# HighVoltageMeasurementModule_1000V.net
KiCad netlist of a schematic drawn in EAGLE
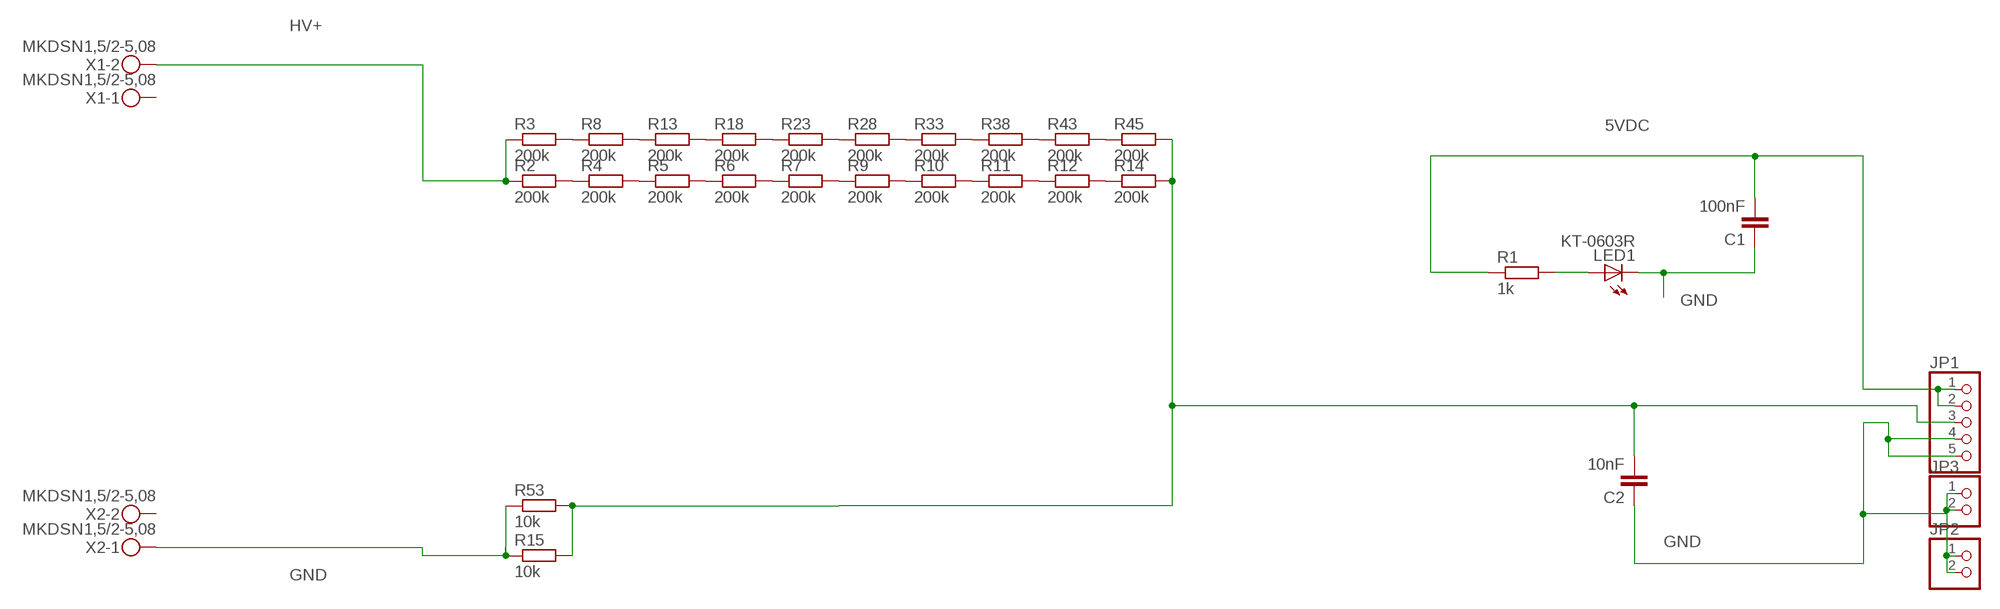
[diagram p0: schematic, sheet 1]

(export (version "E")
  (design (tool "Eeschema 10.0.6"))
  (components
    (comp (ref "C1")
      (value "100nF")
      (footprint "eagle-import:C0805")
      (libsource (lib "eagle-import") (part "C-EUC0805"))
    )
    (comp (ref "C2")
      (value "10nF")
      (footprint "eagle-import:C0805")
      (libsource (lib "eagle-import") (part "C-EUC0805"))
    )
    (comp (ref "JP1")
      (value "PINHD-1X5")
      (footprint "eagle-import:1X05")
      (libsource (lib "eagle-import") (part "PINHD-1X5"))
    )
    (comp (ref "JP2")
      (value "PINHD-1X2")
      (footprint "eagle-import:1X02")
      (libsource (lib "eagle-import") (part "PINHD-1X2"))
    )
    (comp (ref "JP3")
      (value "PINHD-1X2")
      (footprint "eagle-import:1X02")
      (libsource (lib "eagle-import") (part "PINHD-1X2"))
    )
    (comp (ref "LED1")
      (value "KT-0603R")
      (footprint "eagle-import:CHIPLED_0603")
      (libsource (lib "eagle-import") (part "LEDCHIPLED_0603"))
    )
    (comp (ref "R1")
      (value "1k")
      (footprint "eagle-import:R0805")
      (libsource (lib "eagle-import") (part "R-EU_R0805"))
    )
    (comp (ref "R2")
      (value "200k")
      (footprint "eagle-import:R0805")
      (libsource (lib "eagle-import") (part "R-EU_R0805"))
    )
    (comp (ref "R3")
      (value "200k")
      (footprint "eagle-import:R0805")
      (libsource (lib "eagle-import") (part "R-EU_R0805"))
    )
    (comp (ref "R4")
      (value "200k")
      (footprint "eagle-import:R0805")
      (libsource (lib "eagle-import") (part "R-EU_R0805"))
    )
    (comp (ref "R5")
      (value "200k")
      (footprint "eagle-import:R0805")
      (libsource (lib "eagle-import") (part "R-EU_R0805"))
    )
    (comp (ref "R6")
      (value "200k")
      (footprint "eagle-import:R0805")
      (libsource (lib "eagle-import") (part "R-EU_R0805"))
    )
    (comp (ref "R7")
      (value "200k")
      (footprint "eagle-import:R0805")
      (libsource (lib "eagle-import") (part "R-EU_R0805"))
    )
    (comp (ref "R8")
      (value "200k")
      (footprint "eagle-import:R0805")
      (libsource (lib "eagle-import") (part "R-EU_R0805"))
    )
    (comp (ref "R9")
      (value "200k")
      (footprint "eagle-import:R0805")
      (libsource (lib "eagle-import") (part "R-EU_R0805"))
    )
    (comp (ref "R10")
      (value "200k")
      (footprint "eagle-import:R0805")
      (libsource (lib "eagle-import") (part "R-EU_R0805"))
    )
    (comp (ref "R11")
      (value "200k")
      (footprint "eagle-import:R0805")
      (libsource (lib "eagle-import") (part "R-EU_R0805"))
    )
    (comp (ref "R12")
      (value "200k")
      (footprint "eagle-import:R0805")
      (libsource (lib "eagle-import") (part "R-EU_R0805"))
    )
    (comp (ref "R13")
      (value "200k")
      (footprint "eagle-import:R0805")
      (libsource (lib "eagle-import") (part "R-EU_R0805"))
    )
    (comp (ref "R14")
      (value "200k")
      (footprint "eagle-import:R0805")
      (libsource (lib "eagle-import") (part "R-EU_R0805"))
    )
    (comp (ref "R15")
      (value "10k")
      (footprint "eagle-import:R0805")
      (libsource (lib "eagle-import") (part "R-EU_R0805"))
    )
    (comp (ref "R18")
      (value "200k")
      (footprint "eagle-import:R0805")
      (libsource (lib "eagle-import") (part "R-EU_R0805"))
    )
    (comp (ref "R23")
      (value "200k")
      (footprint "eagle-import:R0805")
      (libsource (lib "eagle-import") (part "R-EU_R0805"))
    )
    (comp (ref "R28")
      (value "200k")
      (footprint "eagle-import:R0805")
      (libsource (lib "eagle-import") (part "R-EU_R0805"))
    )
    (comp (ref "R33")
      (value "200k")
      (footprint "eagle-import:R0805")
      (libsource (lib "eagle-import") (part "R-EU_R0805"))
    )
    (comp (ref "R38")
      (value "200k")
      (footprint "eagle-import:R0805")
      (libsource (lib "eagle-import") (part "R-EU_R0805"))
    )
    (comp (ref "R43")
      (value "200k")
      (footprint "eagle-import:R0805")
      (libsource (lib "eagle-import") (part "R-EU_R0805"))
    )
    (comp (ref "R45")
      (value "200k")
      (footprint "eagle-import:R0805")
      (libsource (lib "eagle-import") (part "R-EU_R0805"))
    )
    (comp (ref "R53")
      (value "10k")
      (footprint "eagle-import:R0805")
      (libsource (lib "eagle-import") (part "R-EU_R0805"))
    )
    (comp (ref "X1")
      (value "MKDSN1,5/2-5,08")
      (footprint "eagle-import:MKDSN1,5_2-5,08")
      (libsource (lib "eagle-import") (part "MKDSN1,5/2-5,08"))
    )
    (comp (ref "X2")
      (value "MKDSN1,5/2-5,08")
      (footprint "eagle-import:MKDSN1,5_2-5,08")
      (libsource (lib "eagle-import") (part "MKDSN1,5/2-5,08"))
    )
  )
  (nets
    (net (code "1") (name "/5VDC") (class "Default")
      (node (ref "C1") (pin "2") (pinfunction "2_2") (pintype "passive"))
      (node (ref "JP1") (pin "1") (pinfunction "1_1") (pintype "passive"))
      (node (ref "JP1") (pin "2") (pinfunction "2_2") (pintype "passive"))
      (node (ref "R1") (pin "1") (pinfunction "1_1") (pintype "passive"))
    )
    (net (code "2") (name "/GND") (class "Default")
      (node (ref "C1") (pin "1") (pinfunction "1_1") (pintype "passive"))
      (node (ref "C2") (pin "1") (pinfunction "1_1") (pintype "passive"))
      (node (ref "JP1") (pin "4") (pinfunction "4_4") (pintype "passive"))
      (node (ref "JP1") (pin "5") (pinfunction "5_5") (pintype "passive"))
      (node (ref "JP2") (pin "1") (pinfunction "1_1") (pintype "passive"))
      (node (ref "JP2") (pin "2") (pinfunction "2_2") (pintype "passive"))
      (node (ref "JP3") (pin "1") (pinfunction "1_1") (pintype "passive"))
      (node (ref "JP3") (pin "2") (pinfunction "2_2") (pintype "passive"))
      (node (ref "LED1") (pin "C") (pinfunction "C_C") (pintype "passive"))
      (node (ref "R15") (pin "1") (pinfunction "1_1") (pintype "passive"))
      (node (ref "R53") (pin "1") (pinfunction "1_1") (pintype "passive"))
      (node (ref "X2") (pin "1") (pinfunction "KL_1") (pintype "passive"))
    )
    (net (code "3") (name "/HV+") (class "Default")
      (node (ref "R2") (pin "1") (pinfunction "1_1") (pintype "passive"))
      (node (ref "R3") (pin "1") (pinfunction "1_1") (pintype "passive"))
      (node (ref "X1") (pin "2") (pinfunction "KL_2") (pintype "passive"))
    )
    (net (code "4") (name "Net-(C2-Pad2)") (class "Default")
      (node (ref "C2") (pin "2") (pinfunction "2_2") (pintype "passive"))
      (node (ref "JP1") (pin "3") (pinfunction "3_3") (pintype "passive"))
      (node (ref "R14") (pin "2") (pinfunction "2_2") (pintype "passive"))
      (node (ref "R15") (pin "2") (pinfunction "2_2") (pintype "passive"))
      (node (ref "R45") (pin "2") (pinfunction "2_2") (pintype "passive"))
      (node (ref "R53") (pin "2") (pinfunction "2_2") (pintype "passive"))
    )
    (net (code "5") (name "Net-(LED1-PadA)") (class "Default")
      (node (ref "LED1") (pin "A") (pinfunction "A_A") (pintype "passive"))
      (node (ref "R1") (pin "2") (pinfunction "2_2") (pintype "passive"))
    )
    (net (code "6") (name "Net-(R2-Pad2)") (class "Default")
      (node (ref "R2") (pin "2") (pinfunction "2_2") (pintype "passive"))
      (node (ref "R4") (pin "1") (pinfunction "1_1") (pintype "passive"))
    )
    (net (code "7") (name "Net-(R3-Pad2)") (class "Default")
      (node (ref "R3") (pin "2") (pinfunction "2_2") (pintype "passive"))
      (node (ref "R8") (pin "1") (pinfunction "1_1") (pintype "passive"))
    )
    (net (code "8") (name "Net-(R4-Pad2)") (class "Default")
      (node (ref "R4") (pin "2") (pinfunction "2_2") (pintype "passive"))
      (node (ref "R5") (pin "1") (pinfunction "1_1") (pintype "passive"))
    )
    (net (code "9") (name "Net-(R5-Pad2)") (class "Default")
      (node (ref "R5") (pin "2") (pinfunction "2_2") (pintype "passive"))
      (node (ref "R6") (pin "1") (pinfunction "1_1") (pintype "passive"))
    )
    (net (code "10") (name "Net-(R6-Pad2)") (class "Default")
      (node (ref "R6") (pin "2") (pinfunction "2_2") (pintype "passive"))
      (node (ref "R7") (pin "1") (pinfunction "1_1") (pintype "passive"))
    )
    (net (code "11") (name "Net-(R7-Pad2)") (class "Default")
      (node (ref "R7") (pin "2") (pinfunction "2_2") (pintype "passive"))
      (node (ref "R9") (pin "1") (pinfunction "1_1") (pintype "passive"))
    )
    (net (code "12") (name "Net-(R10-Pad1)") (class "Default")
      (node (ref "R10") (pin "1") (pinfunction "1_1") (pintype "passive"))
      (node (ref "R9") (pin "2") (pinfunction "2_2") (pintype "passive"))
    )
    (net (code "13") (name "Net-(R10-Pad2)") (class "Default")
      (node (ref "R10") (pin "2") (pinfunction "2_2") (pintype "passive"))
      (node (ref "R11") (pin "1") (pinfunction "1_1") (pintype "passive"))
    )
    (net (code "14") (name "Net-(R11-Pad2)") (class "Default")
      (node (ref "R11") (pin "2") (pinfunction "2_2") (pintype "passive"))
      (node (ref "R12") (pin "1") (pinfunction "1_1") (pintype "passive"))
    )
    (net (code "15") (name "Net-(R12-Pad2)") (class "Default")
      (node (ref "R12") (pin "2") (pinfunction "2_2") (pintype "passive"))
      (node (ref "R14") (pin "1") (pinfunction "1_1") (pintype "passive"))
    )
    (net (code "16") (name "Net-(R13-Pad1)") (class "Default")
      (node (ref "R13") (pin "1") (pinfunction "1_1") (pintype "passive"))
      (node (ref "R8") (pin "2") (pinfunction "2_2") (pintype "passive"))
    )
    (net (code "17") (name "Net-(R13-Pad2)") (class "Default")
      (node (ref "R13") (pin "2") (pinfunction "2_2") (pintype "passive"))
      (node (ref "R18") (pin "1") (pinfunction "1_1") (pintype "passive"))
    )
    (net (code "18") (name "Net-(R18-Pad2)") (class "Default")
      (node (ref "R18") (pin "2") (pinfunction "2_2") (pintype "passive"))
      (node (ref "R23") (pin "1") (pinfunction "1_1") (pintype "passive"))
    )
    (net (code "19") (name "Net-(R23-Pad2)") (class "Default")
      (node (ref "R23") (pin "2") (pinfunction "2_2") (pintype "passive"))
      (node (ref "R28") (pin "1") (pinfunction "1_1") (pintype "passive"))
    )
    (net (code "20") (name "Net-(R28-Pad2)") (class "Default")
      (node (ref "R28") (pin "2") (pinfunction "2_2") (pintype "passive"))
      (node (ref "R33") (pin "1") (pinfunction "1_1") (pintype "passive"))
    )
    (net (code "21") (name "Net-(R33-Pad2)") (class "Default")
      (node (ref "R33") (pin "2") (pinfunction "2_2") (pintype "passive"))
      (node (ref "R38") (pin "1") (pinfunction "1_1") (pintype "passive"))
    )
    (net (code "22") (name "Net-(R38-Pad2)") (class "Default")
      (node (ref "R38") (pin "2") (pinfunction "2_2") (pintype "passive"))
      (node (ref "R43") (pin "1") (pinfunction "1_1") (pintype "passive"))
    )
    (net (code "23") (name "Net-(R43-Pad2)") (class "Default")
      (node (ref "R43") (pin "2") (pinfunction "2_2") (pintype "passive"))
      (node (ref "R45") (pin "1") (pinfunction "1_1") (pintype "passive"))
    )
    (net (code "24") (name "unconnected-(X1A-KL-Pad1)") (class "Default")
      (node (ref "X1") (pin "1") (pinfunction "KL_1") (pintype "passive"))
    )
    (net (code "25") (name "unconnected-(X2B-KL-Pad2)") (class "Default")
      (node (ref "X2") (pin "2") (pinfunction "KL_2") (pintype "passive"))
    )
  )
)
